# linearni_zdroj.net
KiCad netlist of a schematic drawn in EAGLE
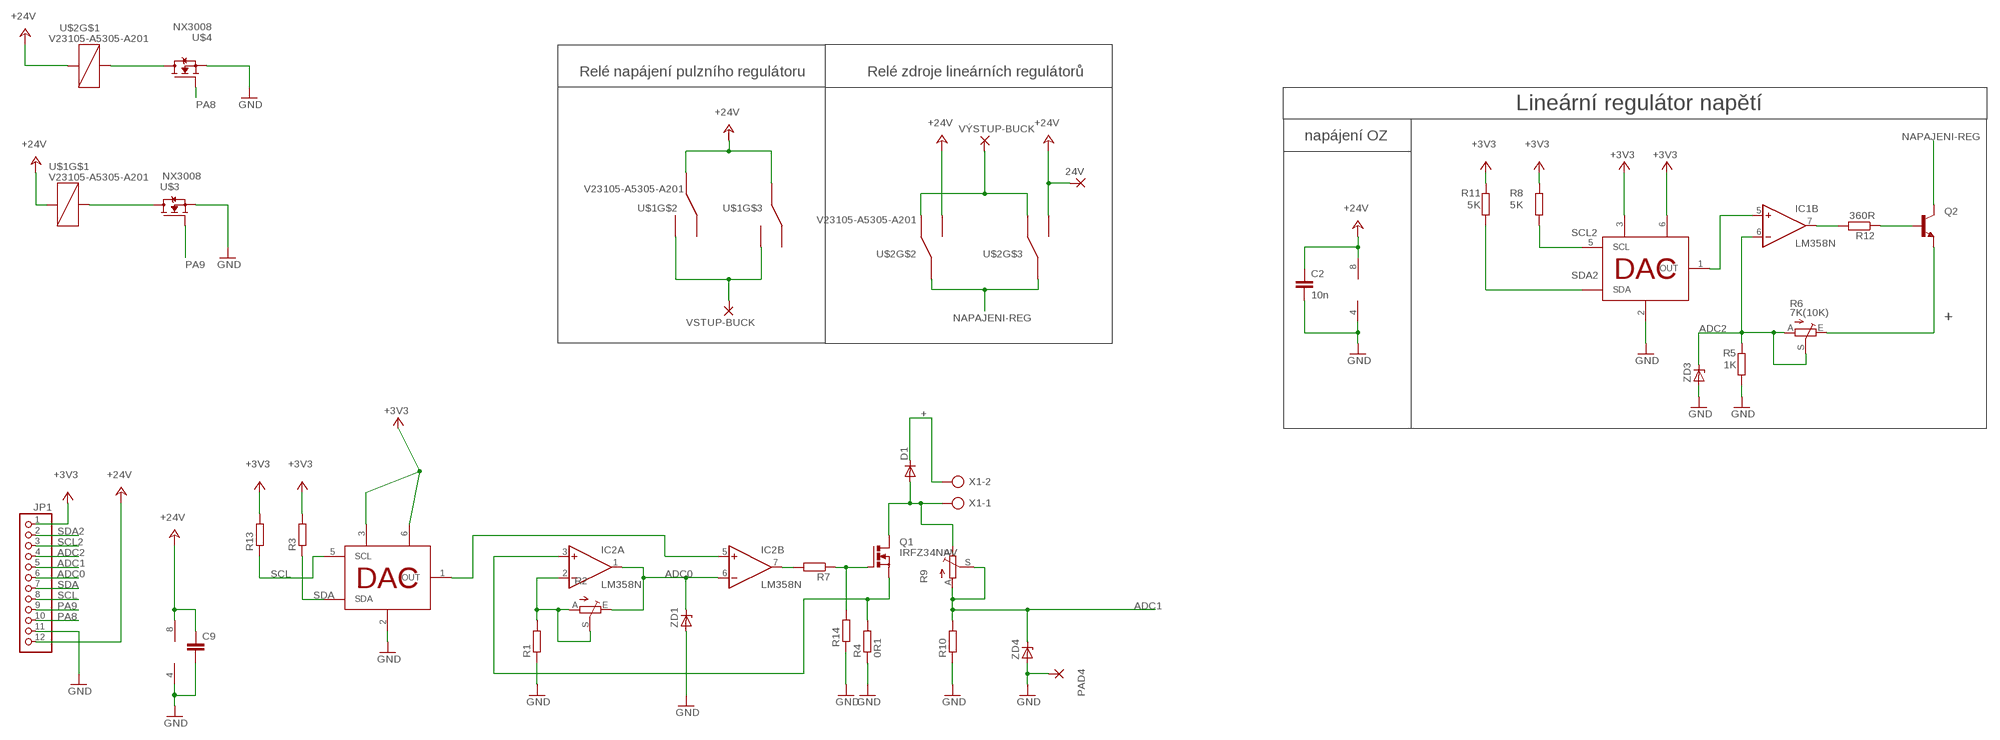
[diagram p0: schematic, sheet 1]

(export (version "E")
  (design (tool "Eeschema 10.0.6"))
  (components
    (comp (ref "24V")
      (value "3,81/1,4")
      (footprint "eagle-import:3,81_1,4")
      (libsource (lib "eagle-import") (part "3,81/1,4"))
    )
    (comp (ref "C2")
      (value "10n")
      (footprint "eagle-import:C0805")
      (libsource (lib "eagle-import") (part "C-EUC0805"))
    )
    (comp (ref "C9")
      (value "C-EUC0805")
      (footprint "eagle-import:C0805")
      (libsource (lib "eagle-import") (part "C-EUC0805"))
    )
    (comp (ref "D1")
      (value "DIODE7")
      (footprint "eagle-import:DO35-7B")
      (libsource (lib "eagle-import") (part "DIODE7"))
    )
    (comp (ref "IC1")
      (value "LM358N")
      (footprint "eagle-import:DIL08")
      (libsource (lib "eagle-import") (part "LM358N"))
    )
    (comp (ref "IC2")
      (value "LM358N")
      (footprint "eagle-import:DIL08")
      (libsource (lib "eagle-import") (part "LM358N"))
    )
    (comp (ref "JP1")
      (value "PINHD-1X12")
      (footprint "eagle-import:1X12")
      (libsource (lib "eagle-import") (part "PINHD-1X12"))
    )
    (comp (ref "PAD4")
      (value "3,81/1,4")
      (footprint "eagle-import:3,81_1,4")
      (libsource (lib "eagle-import") (part "3,81/1,4"))
    )
    (comp (ref "Q1")
      (value "IRFZ34NAV")
      (footprint "eagle-import:TO220AV")
      (libsource (lib "eagle-import") (part "IRFZ34NAV"))
    )
    (comp (ref "Q2")
      (value "-NPN-TO220V")
      (footprint "eagle-import:TO220V")
      (libsource (lib "eagle-import") (part "-NPN-TO220V"))
    )
    (comp (ref "R1")
      (value "R-EU_R0805")
      (footprint "eagle-import:R0805")
      (libsource (lib "eagle-import") (part "R-EU_R0805"))
    )
    (comp (ref "R2")
      (value "TRIM_EU-CA6V")
      (footprint "eagle-import:CA6V")
      (libsource (lib "eagle-import") (part "TRIM_EU-CA6V"))
    )
    (comp (ref "R3")
      (value "R-EU_R0805")
      (footprint "eagle-import:R0805")
      (libsource (lib "eagle-import") (part "R-EU_R0805"))
    )
    (comp (ref "R4")
      (value "0R1")
      (footprint "eagle-import:0411_15")
      (libsource (lib "eagle-import") (part "R-EU_0411/15"))
    )
    (comp (ref "R5")
      (value "1K")
      (footprint "eagle-import:R0805")
      (libsource (lib "eagle-import") (part "R-EU_R0805"))
    )
    (comp (ref "R6")
      (value "7K(10K)")
      (footprint "eagle-import:CA6V")
      (libsource (lib "eagle-import") (part "TRIM_EU-CA6V"))
    )
    (comp (ref "R7")
      (value "R-EU_R0805")
      (footprint "eagle-import:R0805")
      (libsource (lib "eagle-import") (part "R-EU_R0805"))
    )
    (comp (ref "R8")
      (value "5K")
      (footprint "eagle-import:R0805")
      (libsource (lib "eagle-import") (part "R-EU_R0805"))
    )
    (comp (ref "R9")
      (value "TRIM_EU-CA6V")
      (footprint "eagle-import:CA6V")
      (libsource (lib "eagle-import") (part "TRIM_EU-CA6V"))
    )
    (comp (ref "R10")
      (value "R-EU_R0805")
      (footprint "eagle-import:R0805")
      (libsource (lib "eagle-import") (part "R-EU_R0805"))
    )
    (comp (ref "R11")
      (value "5K")
      (footprint "eagle-import:R0805")
      (libsource (lib "eagle-import") (part "R-EU_R0805"))
    )
    (comp (ref "R12")
      (value "360R")
      (footprint "eagle-import:R0805")
      (libsource (lib "eagle-import") (part "R-EU_R0805"))
    )
    (comp (ref "R13")
      (value "R-EU_R0805")
      (footprint "eagle-import:R0805")
      (libsource (lib "eagle-import") (part "R-EU_R0805"))
    )
    (comp (ref "R14")
      (value "R-EU_R0805")
      (footprint "eagle-import:R0805")
      (libsource (lib "eagle-import") (part "R-EU_R0805"))
    )
    (comp (ref "U$1")
      (value "V23105-A5305-A201")
      (footprint "eagle-import:V23105-A5305-A201")
      (libsource (lib "eagle-import") (part "V23105-A5305-A201"))
    )
    (comp (ref "U$2")
      (value "V23105-A5305-A201")
      (footprint "eagle-import:V23105-A5305-A201")
      (libsource (lib "eagle-import") (part "V23105-A5305-A201"))
    )
    (comp (ref "U$3")
      (value "NX3008")
      (footprint "eagle-import:SOT95P240X110-3N")
      (libsource (lib "eagle-import") (part "NX3008"))
    )
    (comp (ref "U$4")
      (value "NX3008")
      (footprint "eagle-import:SOT95P240X110-3N")
      (libsource (lib "eagle-import") (part "NX3008"))
    )
    (comp (ref "U$5")
      (value "MCP4726")
      (footprint "eagle-import:TSOT23-6")
      (libsource (lib "eagle-import") (part "MCP4726"))
    )
    (comp (ref "U$6")
      (value "MCP4726")
      (footprint "eagle-import:TSOT23-6")
      (libsource (lib "eagle-import") (part "MCP4726"))
    )
    (comp (ref "VSTUP-BUCK")
      (value "3,81/1,4")
      (footprint "eagle-import:3,81_1,4")
      (libsource (lib "eagle-import") (part "3,81/1,4"))
    )
    (comp (ref "VÝSTUP-BUCK")
      (value "3,81/1,4")
      (footprint "eagle-import:3,81_1,4")
      (libsource (lib "eagle-import") (part "3,81/1,4"))
    )
    (comp (ref "X1")
      (value "AK500/2")
      (footprint "eagle-import:AK500_2")
      (libsource (lib "eagle-import") (part "AK500/2"))
    )
    (comp (ref "ZD1")
      (value "DIODE_ZENER\"2")
      (footprint "eagle-import:MINIMELF")
      (libsource (lib "eagle-import") (part "DIODE_ZENER{dblquote}2"))
    )
    (comp (ref "ZD3")
      (value "DIODE_ZENER\"2")
      (footprint "eagle-import:MINIMELF")
      (libsource (lib "eagle-import") (part "DIODE_ZENER{dblquote}2"))
    )
    (comp (ref "ZD4")
      (value "DIODE_ZENER\"2")
      (footprint "eagle-import:MINIMELF")
      (libsource (lib "eagle-import") (part "DIODE_ZENER{dblquote}2"))
    )
  )
  (nets
    (net (code "1") (name "+3V3") (class "Default")
      (node (ref "JP1") (pin "1") (pinfunction "1_1") (pintype "passive"))
      (node (ref "R11") (pin "2") (pinfunction "2_2") (pintype "passive"))
      (node (ref "R13") (pin "2") (pinfunction "2_2") (pintype "passive"))
      (node (ref "R3") (pin "2") (pinfunction "2_2") (pintype "passive"))
      (node (ref "R8") (pin "2") (pinfunction "2_2") (pintype "passive"))
      (node (ref "U$5") (pin "3") (pinfunction "VDD_3") (pintype "bidirectional"))
      (node (ref "U$5") (pin "6") (pinfunction "VREF_6") (pintype "bidirectional"))
      (node (ref "U$6") (pin "3") (pinfunction "VDD_3") (pintype "bidirectional"))
      (node (ref "U$6") (pin "6") (pinfunction "VREF_6") (pintype "bidirectional"))
    )
    (net (code "2") (name "+24V") (class "Default")
      (node (ref "24V") (pin "1") (pinfunction "P_1") (pintype "passive"))
      (node (ref "C2") (pin "1") (pinfunction "1_1") (pintype "passive"))
      (node (ref "C9") (pin "1") (pinfunction "1_1") (pintype "passive"))
      (node (ref "IC1") (pin "8") (pinfunction "V+_8") (pintype "power_in"))
      (node (ref "IC2") (pin "8") (pinfunction "V+_8") (pintype "power_in"))
      (node (ref "JP1") (pin "12") (pinfunction "12_12") (pintype "passive"))
      (node (ref "U$1") (pin "1") (pinfunction "C$1_1") (pintype "input"))
      (node (ref "U$1") (pin "13") (pinfunction "1_13") (pintype "bidirectional"))
      (node (ref "U$1") (pin "4") (pinfunction "1_4") (pintype "bidirectional"))
      (node (ref "U$2") (pin "1") (pinfunction "C$1_1") (pintype "input"))
      (node (ref "U$2") (pin "8") (pinfunction "3_8") (pintype "bidirectional"))
      (node (ref "U$2") (pin "9") (pinfunction "3_9") (pintype "bidirectional"))
    )
    (net (code "3") (name "/+") (class "Default")
      (node (ref "D1") (pin "C") (pinfunction "C_C") (pintype "passive"))
      (node (ref "Q2") (pin "3") (pinfunction "E_3") (pintype "passive"))
      (node (ref "R6") (pin "E") (pinfunction "E_E") (pintype "passive"))
      (node (ref "X1") (pin "2") (pinfunction "KL_2") (pintype "passive"))
    )
    (net (code "4") (name "/ADC0") (class "Default")
      (node (ref "IC2") (pin "1") (pinfunction "OUT_1") (pintype "output"))
      (node (ref "IC2") (pin "6") (pinfunction "-IN_6") (pintype "input"))
      (node (ref "JP1") (pin "6") (pinfunction "6_6") (pintype "passive"))
      (node (ref "R2") (pin "E") (pinfunction "E_E") (pintype "passive"))
      (node (ref "ZD1") (pin "C") (pinfunction "C_C") (pintype "passive"))
    )
    (net (code "5") (name "/ADC1") (class "Default")
      (node (ref "JP1") (pin "5") (pinfunction "5_5") (pintype "passive"))
      (node (ref "R10") (pin "2") (pinfunction "2_2") (pintype "passive"))
      (node (ref "R9") (pin "A") (pinfunction "A_A") (pintype "passive"))
      (node (ref "R9") (pin "S") (pinfunction "S_S") (pintype "passive"))
      (node (ref "ZD4") (pin "C") (pinfunction "C_C") (pintype "passive"))
    )
    (net (code "6") (name "/ADC2") (class "Default")
      (node (ref "IC1") (pin "6") (pinfunction "-IN_6") (pintype "input"))
      (node (ref "JP1") (pin "4") (pinfunction "4_4") (pintype "passive"))
      (node (ref "R5") (pin "2") (pinfunction "2_2") (pintype "passive"))
      (node (ref "R6") (pin "A") (pinfunction "A_A") (pintype "passive"))
      (node (ref "R6") (pin "S") (pinfunction "S_S") (pintype "passive"))
      (node (ref "ZD3") (pin "C") (pinfunction "C_C") (pintype "passive"))
    )
    (net (code "7") (name "/NAPAJENI-REG") (class "Default")
      (node (ref "Q2") (pin "2") (pinfunction "C_2") (pintype "passive"))
      (node (ref "U$2") (pin "13") (pinfunction "1_13") (pintype "bidirectional"))
      (node (ref "U$2") (pin "4") (pinfunction "1_4") (pintype "bidirectional"))
    )
    (net (code "8") (name "/PA8") (class "Default")
      (node (ref "JP1") (pin "10") (pinfunction "10_10") (pintype "passive"))
      (node (ref "U$4") (pin "1") (pinfunction "G_1") (pintype "passive"))
    )
    (net (code "9") (name "/PA9") (class "Default")
      (node (ref "JP1") (pin "9") (pinfunction "9_9") (pintype "passive"))
      (node (ref "U$3") (pin "1") (pinfunction "G_1") (pintype "passive"))
    )
    (net (code "10") (name "/SCL") (class "Default")
      (node (ref "JP1") (pin "8") (pinfunction "8_8") (pintype "passive"))
      (node (ref "R13") (pin "1") (pinfunction "1_1") (pintype "passive"))
      (node (ref "U$5") (pin "5") (pinfunction "SCL_5") (pintype "bidirectional"))
    )
    (net (code "11") (name "/SCL2") (class "Default")
      (node (ref "JP1") (pin "3") (pinfunction "3_3") (pintype "passive"))
      (node (ref "R8") (pin "1") (pinfunction "1_1") (pintype "passive"))
      (node (ref "U$6") (pin "5") (pinfunction "SCL_5") (pintype "bidirectional"))
    )
    (net (code "12") (name "/SDA") (class "Default")
      (node (ref "JP1") (pin "7") (pinfunction "7_7") (pintype "passive"))
      (node (ref "R3") (pin "1") (pinfunction "1_1") (pintype "passive"))
      (node (ref "U$5") (pin "4") (pinfunction "SDA_4") (pintype "bidirectional"))
    )
    (net (code "13") (name "/SDA2") (class "Default")
      (node (ref "JP1") (pin "2") (pinfunction "2_2") (pintype "passive"))
      (node (ref "R11") (pin "1") (pinfunction "1_1") (pintype "passive"))
      (node (ref "U$6") (pin "4") (pinfunction "SDA_4") (pintype "bidirectional"))
    )
    (net (code "14") (name "GND") (class "Default")
      (node (ref "C2") (pin "2") (pinfunction "2_2") (pintype "passive"))
      (node (ref "C9") (pin "2") (pinfunction "2_2") (pintype "passive"))
      (node (ref "IC1") (pin "4") (pinfunction "V-_4") (pintype "power_in"))
      (node (ref "IC2") (pin "4") (pinfunction "V-_4") (pintype "power_in"))
      (node (ref "JP1") (pin "11") (pinfunction "11_11") (pintype "passive"))
      (node (ref "PAD4") (pin "1") (pinfunction "P_1") (pintype "passive"))
      (node (ref "R1") (pin "1") (pinfunction "1_1") (pintype "passive"))
      (node (ref "R10") (pin "1") (pinfunction "1_1") (pintype "passive"))
      (node (ref "R14") (pin "1") (pinfunction "1_1") (pintype "passive"))
      (node (ref "R4") (pin "1") (pinfunction "1_1") (pintype "passive"))
      (node (ref "R5") (pin "1") (pinfunction "1_1") (pintype "passive"))
      (node (ref "U$3") (pin "2") (pinfunction "S_2") (pintype "passive"))
      (node (ref "U$4") (pin "2") (pinfunction "S_2") (pintype "passive"))
      (node (ref "U$5") (pin "2") (pinfunction "VSS_2") (pintype "bidirectional"))
      (node (ref "U$6") (pin "2") (pinfunction "VSS_2") (pintype "bidirectional"))
      (node (ref "ZD1") (pin "A") (pinfunction "A_A") (pintype "passive"))
      (node (ref "ZD3") (pin "A") (pinfunction "A_A") (pintype "passive"))
      (node (ref "ZD4") (pin "A") (pinfunction "A_A") (pintype "passive"))
    )
    (net (code "15") (name "Net-(IC1B-+IN)") (class "Default")
      (node (ref "IC1") (pin "5") (pinfunction "+IN_5") (pintype "input"))
      (node (ref "U$6") (pin "1") (pinfunction "OUT_1") (pintype "bidirectional"))
    )
    (net (code "16") (name "Net-(IC1B-OUT)") (class "Default")
      (node (ref "IC1") (pin "7") (pinfunction "OUT_7") (pintype "output"))
      (node (ref "R12") (pin "2") (pinfunction "2_2") (pintype "passive"))
    )
    (net (code "17") (name "Net-(IC2A-+IN)") (class "Default")
      (node (ref "IC2") (pin "3") (pinfunction "+IN_3") (pintype "input"))
      (node (ref "Q1") (pin "S") (pinfunction "S_S") (pintype "passive"))
      (node (ref "R4") (pin "2") (pinfunction "2_2") (pintype "passive"))
    )
    (net (code "18") (name "Net-(IC2A--IN)") (class "Default")
      (node (ref "IC2") (pin "2") (pinfunction "-IN_2") (pintype "input"))
      (node (ref "R1") (pin "2") (pinfunction "2_2") (pintype "passive"))
      (node (ref "R2") (pin "A") (pinfunction "A_A") (pintype "passive"))
      (node (ref "R2") (pin "S") (pinfunction "S_S") (pintype "passive"))
    )
    (net (code "19") (name "Net-(IC2B-+IN)") (class "Default")
      (node (ref "IC2") (pin "5") (pinfunction "+IN_5") (pintype "input"))
      (node (ref "U$5") (pin "1") (pinfunction "OUT_1") (pintype "bidirectional"))
    )
    (net (code "20") (name "Net-(IC2B-OUT)") (class "Default")
      (node (ref "IC2") (pin "7") (pinfunction "OUT_7") (pintype "output"))
      (node (ref "R7") (pin "2") (pinfunction "2_2") (pintype "passive"))
    )
    (net (code "21") (name "Net-(Q1-PadG)") (class "Default")
      (node (ref "Q1") (pin "G") (pinfunction "G_G") (pintype "passive"))
      (node (ref "R14") (pin "2") (pinfunction "2_2") (pintype "passive"))
      (node (ref "R7") (pin "1") (pinfunction "1_1") (pintype "passive"))
    )
    (net (code "22") (name "Net-(Q2-B)") (class "Default")
      (node (ref "Q2") (pin "1") (pinfunction "B_1") (pintype "passive"))
      (node (ref "R12") (pin "1") (pinfunction "1_1") (pintype "passive"))
    )
    (net (code "23") (name "Net-(U$1A-C$2)") (class "Default")
      (node (ref "U$1") (pin "16") (pinfunction "C$2_16") (pintype "input"))
      (node (ref "U$3") (pin "3") (pinfunction "D_3") (pintype "passive"))
    )
    (net (code "24") (name "Net-(U$1B-3)") (class "Default")
      (node (ref "U$1") (pin "8") (pinfunction "3_8") (pintype "bidirectional"))
      (node (ref "U$1") (pin "9") (pinfunction "3_9") (pintype "bidirectional"))
      (node (ref "VSTUP-BUCK") (pin "1") (pinfunction "P_1") (pintype "passive"))
    )
    (net (code "25") (name "Net-(U$2A-C$2)") (class "Default")
      (node (ref "U$2") (pin "16") (pinfunction "C$2_16") (pintype "input"))
      (node (ref "U$4") (pin "3") (pinfunction "D_3") (pintype "passive"))
    )
    (net (code "26") (name "Net-(U$2B-2)") (class "Default")
      (node (ref "U$2") (pin "11") (pinfunction "2_11") (pintype "bidirectional"))
      (node (ref "U$2") (pin "6") (pinfunction "2_6") (pintype "bidirectional"))
      (node (ref "VÝSTUP-BUCK") (pin "1") (pinfunction "P_1") (pintype "passive"))
    )
    (net (code "27") (name "Net-(X1A-KL)") (class "Default")
      (node (ref "D1") (pin "A") (pinfunction "A_A") (pintype "passive"))
      (node (ref "Q1") (pin "D") (pinfunction "D_D") (pintype "passive"))
      (node (ref "R9") (pin "E") (pinfunction "E_E") (pintype "passive"))
      (node (ref "X1") (pin "1") (pinfunction "KL_1") (pintype "passive"))
    )
    (net (code "28") (name "unconnected-(U$1B-2-Pad6)") (class "Default")
      (node (ref "U$1") (pin "6") (pinfunction "2_6") (pintype "bidirectional"))
    )
    (net (code "29") (name "unconnected-(U$1C-2-Pad11)") (class "Default")
      (node (ref "U$1") (pin "11") (pinfunction "2_11") (pintype "bidirectional"))
    )
  )
)
